# PX4FMUv2_4_6_7.net
KiCad netlist of a schematic drawn in Altium Designer
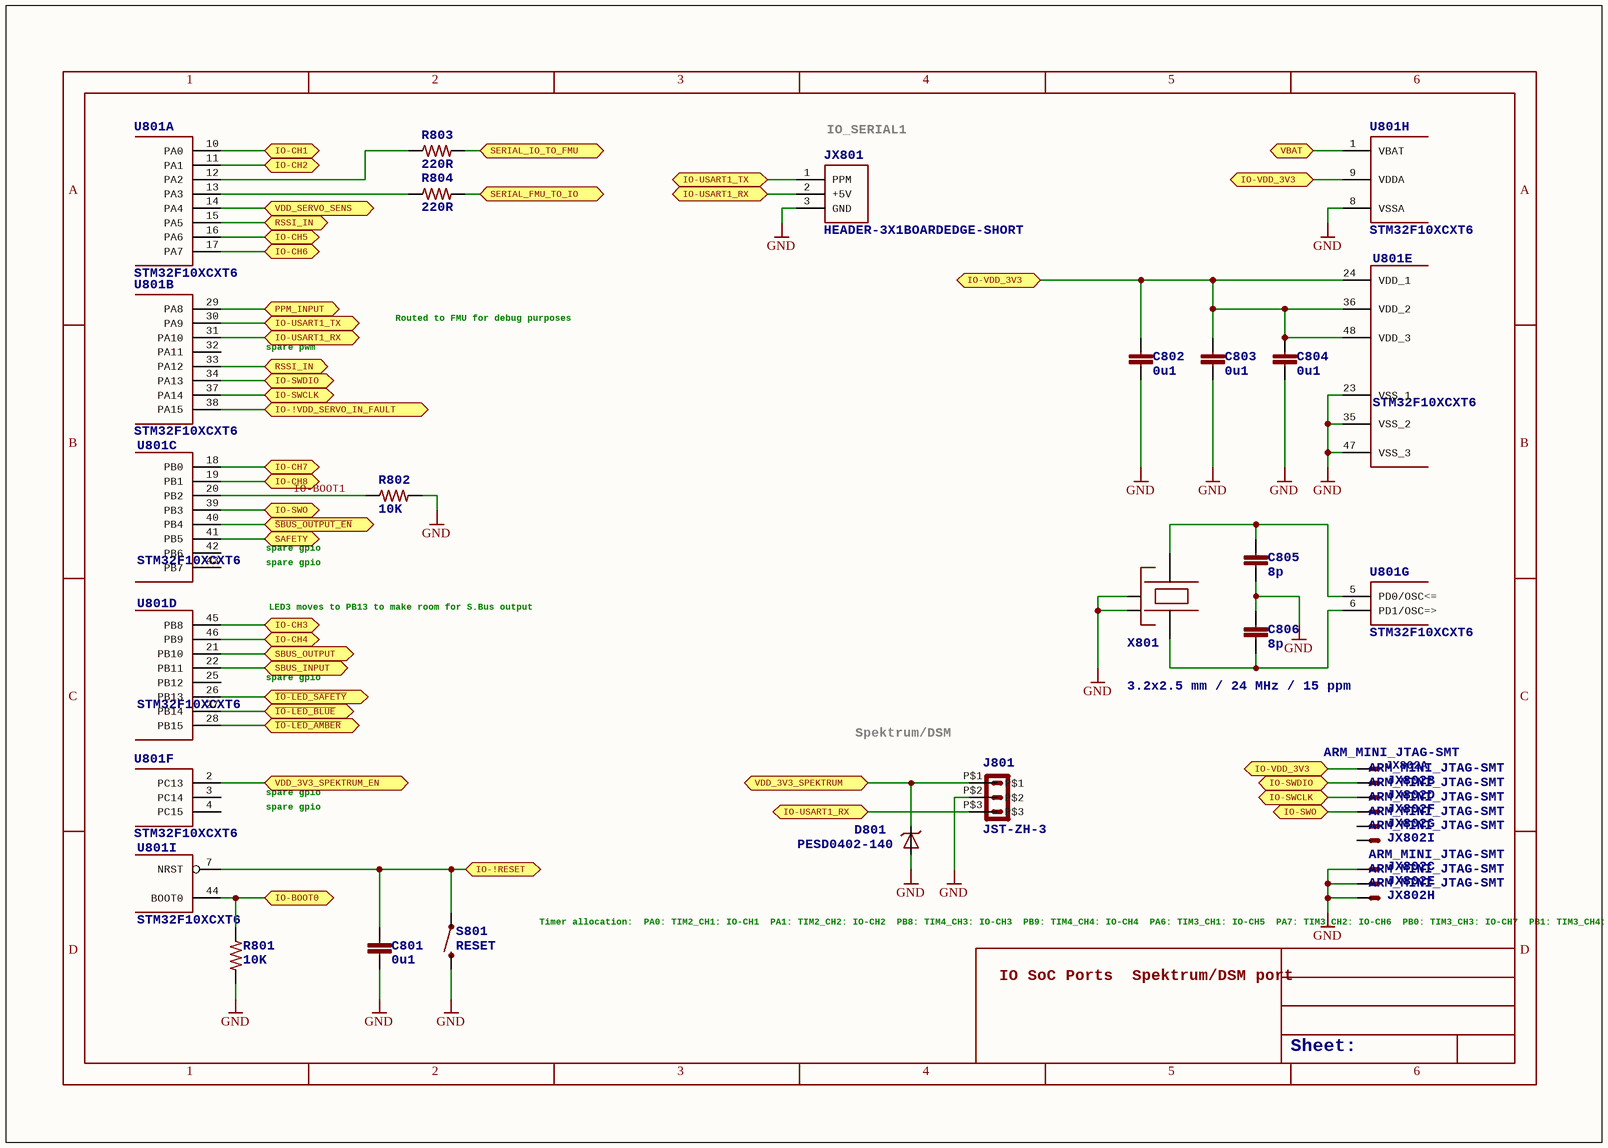
[diagram p0: PX4FMUv2.4.6_7.SchDoc]

(export (version "E")
  (design (tool "Eeschema 10.0.6"))
  (components
    (comp (ref "C801")
      (value "0u1")
      (footprint "0402-CAP")
      (description "CapacitorStandard 0603 ceramic capacitor, and 0.1\" leaded capacitor.")
      (fields (field (name "PARTNO") "CC0402ZRY5V7BB104"))
      (libsource (lib "pixhawk2") (part "CAP0402"))
    )
    (comp (ref "C802")
      (value "0u1")
      (footprint "0402-CAP")
      (description "CapacitorStandard 0603 ceramic capacitor, and 0.1\" leaded capacitor.")
      (fields (field (name "PARTNO") "CC0402ZRY5V7BB104"))
      (libsource (lib "") (part "CAP0402_1"))
    )
    (comp (ref "C803")
      (value "0u1")
      (footprint "0402-CAP")
      (description "CapacitorStandard 0603 ceramic capacitor, and 0.1\" leaded capacitor.")
      (fields (field (name "PARTNO") "CC0402ZRY5V7BB104"))
      (libsource (lib "") (part "CAP0402_1"))
    )
    (comp (ref "C804")
      (value "0u1")
      (footprint "0402-CAP")
      (description "CapacitorStandard 0603 ceramic capacitor, and 0.1\" leaded capacitor.")
      (fields (field (name "PARTNO") "CC0402ZRY5V7BB104"))
      (libsource (lib "") (part "CAP0402_1"))
    )
    (comp (ref "C805")
      (value "8p")
      (footprint "0402-CAP")
      (description "CapacitorStandard 0603 ceramic capacitor, and 0.1\" leaded capacitor.")
      (fields (field (name "PARTNO") "C1005C0G1H080C"))
      (libsource (lib "") (part "CAP0402_1"))
    )
    (comp (ref "C806")
      (value "8p")
      (footprint "0402-CAP")
      (description "CapacitorStandard 0603 ceramic capacitor, and 0.1\" leaded capacitor.")
      (fields (field (name "PARTNO") "C1005C0G1H080C"))
      (libsource (lib "") (part "CAP0402_1"))
    )
    (comp (ref "D801")
      (value "PESD0402-140")
      (footprint "0402-TVS")
      (libsource (lib "pixhawk2") (part "DIODE-TVS"))
    )
    (comp (ref "J801")
      (value "JST-ZH-3")
      (footprint "JST-ZH-SMT-VERTICAL")
      (fields (field (name "PARTNO") "B3B-ZR-SM4-TF (LF)(SN)(P)"))
      (libsource (lib "for-transfers") (part "JST-ZH-3"))
    )
    (comp (ref "JX801")
      (value "HEADER-3X1BOARDEDGE-SHORT")
      (footprint "HEADER_3X01_SMD_H_BOARD_EDGE_SHORT")
      (description "Single row 0.1\" servo header")
      (libsource (lib "pixhawk2") (part "HEADER-3X1BOARDEDGE-SHORT"))
    )
    (comp (ref "JX802")
      (value "ARM_MINI_JTAG-SMT")
      (footprint "FTSH-105-01-XXX-DV-K")
      (description "CONNECTOR   wire to board 1.25 mm (.049 inch) pitch header")
      (fields (field (name "PARTNO") "M50-3900542"))
      (libsource (lib "pixhawk2") (part "ARM_MINI_JTAG-SMT"))
    )
    (comp (ref "R801")
      (value "10K")
      (footprint "0402-RES")
      (fields (field (name "PARTNO") "RC0402FR-0710KL"))
      (libsource (lib "pixhawk2") (part "RESISTOR0402-RES"))
    )
    (comp (ref "R802")
      (value "10K")
      (footprint "0402-RES")
      (fields (field (name "PARTNO") "RC0402FR-0710KL"))
      (libsource (lib "pixhawk2") (part "RESISTOR0402-RES"))
    )
    (comp (ref "R803")
      (value "220R")
      (footprint "0402-RES")
      (fields (field (name "PARTNO") "RC0402FR-07220RL"))
      (libsource (lib "pixhawk2") (part "RESISTOR0402-RES"))
    )
    (comp (ref "R804")
      (value "220R")
      (footprint "0402-RES")
      (fields (field (name "PARTNO") "RC0402FR-07220RL"))
      (libsource (lib "pixhawk2") (part "RESISTOR0402-RES"))
    )
    (comp (ref "S801")
      (value "RESET")
      (footprint "EVQP7J01K")
      (fields (field (name "PARTNO") "EVQ-P7J01P"))
      (libsource (lib "pixhawk2") (part "SWITCH-MOMENTARY-2"))
    )
    (comp (ref "U801")
      (value "STM32F10XCXT6")
      (footprint "TQFP48")
      (description "ST STM32F101/103 48pin LQFP")
      (fields (field (name "PARTNO") "STM32F100C8T6B"))
      (libsource (lib "pixhawk2") (part "STM32F10XCXT6"))
    )
    (comp (ref "X801")
      (value "3.2x2.5 mm / 24 MHz / 15 ppm")
      (footprint "OSCILLATOR-3.2X2.5")
      (description "Crystal Oscillator in 3.2x2.5 SMD")
      (libsource (lib "pixhawk2") (part "OSCILLATOR-3.2X2.5"))
    )
  )
  (nets
    (net (code "1") (name "/IO-!RESET") (class "Default")
      (node (ref "C801") (pin "P$2") (pinfunction "2_P$2") (pintype "passive"))
      (node (ref "S801") (pin "A1") (pinfunction "1_A1") (pintype "passive"))
      (node (ref "U801") (pin "7") (pinfunction "NRST_7") (pintype "passive"))
    )
    (net (code "2") (name "/IO-!VDD_SERVO_IN_FAULT") (class "Default")
      (node (ref "U801") (pin "38") (pinfunction "PA15_38") (pintype "passive"))
    )
    (net (code "3") (name "/IO-BOOT0") (class "Default")
      (node (ref "R801") (pin "P$1") (pinfunction "1_P$1") (pintype "passive"))
      (node (ref "U801") (pin "44") (pinfunction "BOOT0_44") (pintype "passive"))
    )
    (net (code "4") (name "/IO-BOOT1") (class "Default")
      (node (ref "R802") (pin "P$1") (pinfunction "1_P$1") (pintype "passive"))
      (node (ref "U801") (pin "20") (pinfunction "PB2_20") (pintype "passive"))
    )
    (net (code "5") (name "/IO-CH1") (class "Default")
      (node (ref "U801") (pin "10") (pinfunction "PA0_10") (pintype "passive"))
    )
    (net (code "6") (name "/IO-CH2") (class "Default")
      (node (ref "U801") (pin "11") (pinfunction "PA1_11") (pintype "passive"))
    )
    (net (code "7") (name "/IO-CH3") (class "Default")
      (node (ref "U801") (pin "45") (pinfunction "PB8_45") (pintype "passive"))
    )
    (net (code "8") (name "/IO-CH4") (class "Default")
      (node (ref "U801") (pin "46") (pinfunction "PB9_46") (pintype "passive"))
    )
    (net (code "9") (name "/IO-CH5") (class "Default")
      (node (ref "U801") (pin "16") (pinfunction "PA6_16") (pintype "passive"))
    )
    (net (code "10") (name "/IO-CH6") (class "Default")
      (node (ref "U801") (pin "17") (pinfunction "PA7_17") (pintype "passive"))
    )
    (net (code "11") (name "/IO-CH7") (class "Default")
      (node (ref "U801") (pin "18") (pinfunction "PB0_18") (pintype "passive"))
    )
    (net (code "12") (name "/IO-CH8") (class "Default")
      (node (ref "U801") (pin "19") (pinfunction "PB1_19") (pintype "passive"))
    )
    (net (code "13") (name "/IO-SWCLK") (class "Default")
      (node (ref "JX802") (pin "4") (pinfunction "S_4") (pintype "passive"))
      (node (ref "U801") (pin "37") (pinfunction "PA14_37") (pintype "passive"))
    )
    (net (code "14") (name "/IO-SWDIO") (class "Default")
      (node (ref "JX802") (pin "2") (pinfunction "S_2") (pintype "passive"))
      (node (ref "U801") (pin "34") (pinfunction "PA13_34") (pintype "passive"))
    )
    (net (code "15") (name "/IO-SWO") (class "Default")
      (node (ref "JX802") (pin "6") (pinfunction "S_6") (pintype "passive"))
      (node (ref "U801") (pin "39") (pinfunction "PB3_39") (pintype "passive"))
    )
    (net (code "16") (name "/IO-USART1_RX") (class "Default")
      (node (ref "J801") (pin "P$3") (pinfunction "P$3_P$3") (pintype "passive"))
      (node (ref "JX801") (pin "2") (pinfunction "+5V_2") (pintype "passive"))
      (node (ref "U801") (pin "31") (pinfunction "PA10_31") (pintype "passive"))
    )
    (net (code "17") (name "/IO-USART1_TX") (class "Default")
      (node (ref "JX801") (pin "1") (pinfunction "PPM_1") (pintype "passive"))
      (node (ref "U801") (pin "30") (pinfunction "PA9_30") (pintype "passive"))
    )
    (net (code "18") (name "/IO-VDD_3V3") (class "Default")
      (node (ref "C802") (pin "P$1") (pinfunction "1_P$1") (pintype "passive"))
      (node (ref "C803") (pin "P$1") (pinfunction "1_P$1") (pintype "passive"))
      (node (ref "C804") (pin "P$1") (pinfunction "1_P$1") (pintype "passive"))
      (node (ref "JX802") (pin "1") (pinfunction "S_1") (pintype "passive"))
      (node (ref "U801") (pin "24") (pinfunction "VDD_1_24") (pintype "power_in"))
      (node (ref "U801") (pin "36") (pinfunction "VDD_2_36") (pintype "power_in"))
      (node (ref "U801") (pin "48") (pinfunction "VDD_3_48") (pintype "power_in"))
      (node (ref "U801") (pin "9") (pinfunction "VDDA_9") (pintype "power_in"))
    )
    (net (code "19") (name "/PPM_INPUT") (class "Default")
      (node (ref "U801") (pin "29") (pinfunction "PA8_29") (pintype "passive"))
    )
    (net (code "20") (name "/RSSI_IN") (class "Default")
      (node (ref "U801") (pin "15") (pinfunction "PA5_15") (pintype "passive"))
      (node (ref "U801") (pin "33") (pinfunction "PA12_33") (pintype "passive"))
    )
    (net (code "21") (name "/SAFETY") (class "Default")
      (node (ref "U801") (pin "41") (pinfunction "PB5_41") (pintype "passive"))
    )
    (net (code "22") (name "/SBUS_INPUT") (class "Default")
      (node (ref "U801") (pin "22") (pinfunction "PB11_22") (pintype "passive"))
    )
    (net (code "23") (name "/SBUS_OUTPUT") (class "Default")
      (node (ref "U801") (pin "21") (pinfunction "PB10_21") (pintype "passive"))
    )
    (net (code "24") (name "/SERIAL_FMU_TO_IO") (class "Default")
      (node (ref "R804") (pin "P$2") (pinfunction "2_P$2") (pintype "passive"))
    )
    (net (code "25") (name "/SERIAL_IO_TO_FMU") (class "Default")
      (node (ref "R803") (pin "P$2") (pinfunction "2_P$2") (pintype "passive"))
    )
    (net (code "26") (name "/VBAT") (class "Default")
      (node (ref "U801") (pin "1") (pinfunction "VBAT_1") (pintype "power_in"))
    )
    (net (code "27") (name "/VDD_3V3_SPEKTRUM") (class "Default")
      (node (ref "D801") (pin "C") (pinfunction "C_C") (pintype "passive"))
      (node (ref "J801") (pin "P$1") (pinfunction "P$1_P$1") (pintype "passive"))
    )
    (net (code "28") (name "/VDD_3V3_SPEKTRUM_EN") (class "Default")
      (node (ref "U801") (pin "2") (pinfunction "PC13_2") (pintype "passive"))
    )
    (net (code "29") (name "/VDD_SERVO_SENS") (class "Default")
      (node (ref "U801") (pin "14") (pinfunction "PA4_14") (pintype "passive"))
    )
    (net (code "30") (name "/~{IO-LED_AMBER}") (class "Default")
      (node (ref "U801") (pin "28") (pinfunction "PB15_28") (pintype "passive"))
    )
    (net (code "31") (name "/~{IO-LED_BLUE}") (class "Default")
      (node (ref "U801") (pin "27") (pinfunction "PB14_27") (pintype "passive"))
    )
    (net (code "32") (name "/~{IO-LED_SAFETY}") (class "Default")
      (node (ref "U801") (pin "26") (pinfunction "PB13_26") (pintype "passive"))
    )
    (net (code "33") (name "/~{SBUS_OUTPUT_EN}") (class "Default")
      (node (ref "U801") (pin "40") (pinfunction "PB4_40") (pintype "passive"))
    )
    (net (code "34") (name "GND") (class "Default")
      (node (ref "C801") (pin "P$1") (pinfunction "1_P$1") (pintype "passive"))
      (node (ref "C802") (pin "P$2") (pinfunction "2_P$2") (pintype "passive"))
      (node (ref "C803") (pin "P$2") (pinfunction "2_P$2") (pintype "passive"))
      (node (ref "C804") (pin "P$2") (pinfunction "2_P$2") (pintype "passive"))
      (node (ref "C805") (pin "P$2") (pinfunction "2_P$2") (pintype "passive"))
      (node (ref "C806") (pin "P$1") (pinfunction "1_P$1") (pintype "passive"))
      (node (ref "D801") (pin "A") (pinfunction "A_A") (pintype "passive"))
      (node (ref "J801") (pin "P$2") (pinfunction "P$2_P$2") (pintype "passive"))
      (node (ref "JX801") (pin "3") (pinfunction "GND_3") (pintype "passive"))
      (node (ref "JX802") (pin "3") (pinfunction "S_3") (pintype "passive"))
      (node (ref "JX802") (pin "5") (pinfunction "S_5") (pintype "passive"))
      (node (ref "JX802") (pin "9") (pinfunction "S_9") (pintype "passive"))
      (node (ref "R801") (pin "P$2") (pinfunction "2_P$2") (pintype "passive"))
      (node (ref "R802") (pin "P$2") (pinfunction "2_P$2") (pintype "passive"))
      (node (ref "S801") (pin "B3") (pinfunction "2_B3") (pintype "passive"))
      (node (ref "U801") (pin "23") (pinfunction "VSS_1_23") (pintype "power_in"))
      (node (ref "U801") (pin "35") (pinfunction "VSS_2_35") (pintype "power_in"))
      (node (ref "U801") (pin "47") (pinfunction "VSS_3_47") (pintype "power_in"))
      (node (ref "U801") (pin "8") (pinfunction "VSSA_8") (pintype "power_in"))
      (node (ref "X801") (pin "2") (pinfunction "NC_2_2") (pintype "open_emitter"))
      (node (ref "X801") (pin "4") (pinfunction "NC_4_4") (pintype "open_emitter"))
    )
    (net (code "35") (name "Net-(C805-1)") (class "Default")
      (node (ref "C805") (pin "P$1") (pinfunction "1_P$1") (pintype "passive"))
      (node (ref "U801") (pin "5") (pinfunction "PD0/OSC<=_5") (pintype "passive"))
      (node (ref "X801") (pin "3") (pinfunction "3_3") (pintype "passive"))
    )
    (net (code "36") (name "Net-(C806-2)") (class "Default")
      (node (ref "C806") (pin "P$2") (pinfunction "2_P$2") (pintype "passive"))
      (node (ref "U801") (pin "6") (pinfunction "PD1/OSC=>_6") (pintype "passive"))
      (node (ref "X801") (pin "1") (pinfunction "1_1") (pintype "passive"))
    )
    (net (code "37") (name "Net-(R803-1)") (class "Default")
      (node (ref "R803") (pin "P$1") (pinfunction "1_P$1") (pintype "passive"))
      (node (ref "U801") (pin "12") (pinfunction "PA2_12") (pintype "passive"))
    )
    (net (code "38") (name "Net-(R804-1)") (class "Default")
      (node (ref "R804") (pin "P$1") (pinfunction "1_P$1") (pintype "passive"))
      (node (ref "U801") (pin "13") (pinfunction "PA3_13") (pintype "passive"))
    )
    (net (code "39") (name "unconnected-(JX802G-S-Pad8)") (class "Default")
      (node (ref "JX802") (pin "8") (pinfunction "S_8") (pintype "passive"))
    )
    (net (code "40") (name "unconnected-(JX802I-S-Pad10)") (class "Default")
      (node (ref "JX802") (pin "10") (pinfunction "S_10") (pintype "passive"))
    )
    (net (code "41") (name "unconnected-(U801B-PA11-Pad32)") (class "Default")
      (node (ref "U801") (pin "32") (pinfunction "PA11_32") (pintype "passive"))
    )
    (net (code "42") (name "unconnected-(U801C-PB6-Pad42)") (class "Default")
      (node (ref "U801") (pin "42") (pinfunction "PB6_42") (pintype "passive"))
    )
    (net (code "43") (name "unconnected-(U801C-PB7-Pad43)") (class "Default")
      (node (ref "U801") (pin "43") (pinfunction "PB7_43") (pintype "passive"))
    )
    (net (code "44") (name "unconnected-(U801D-PB12-Pad25)") (class "Default")
      (node (ref "U801") (pin "25") (pinfunction "PB12_25") (pintype "passive"))
    )
    (net (code "45") (name "unconnected-(U801F-PC14-Pad3)") (class "Default")
      (node (ref "U801") (pin "3") (pinfunction "PC14_3") (pintype "passive"))
    )
    (net (code "46") (name "unconnected-(U801F-PC15-Pad4)") (class "Default")
      (node (ref "U801") (pin "4") (pinfunction "PC15_4") (pintype "passive"))
    )
  )
)
